# Motortreiber_3_4.net
KiCad netlist of a schematic drawn in Altium Designer
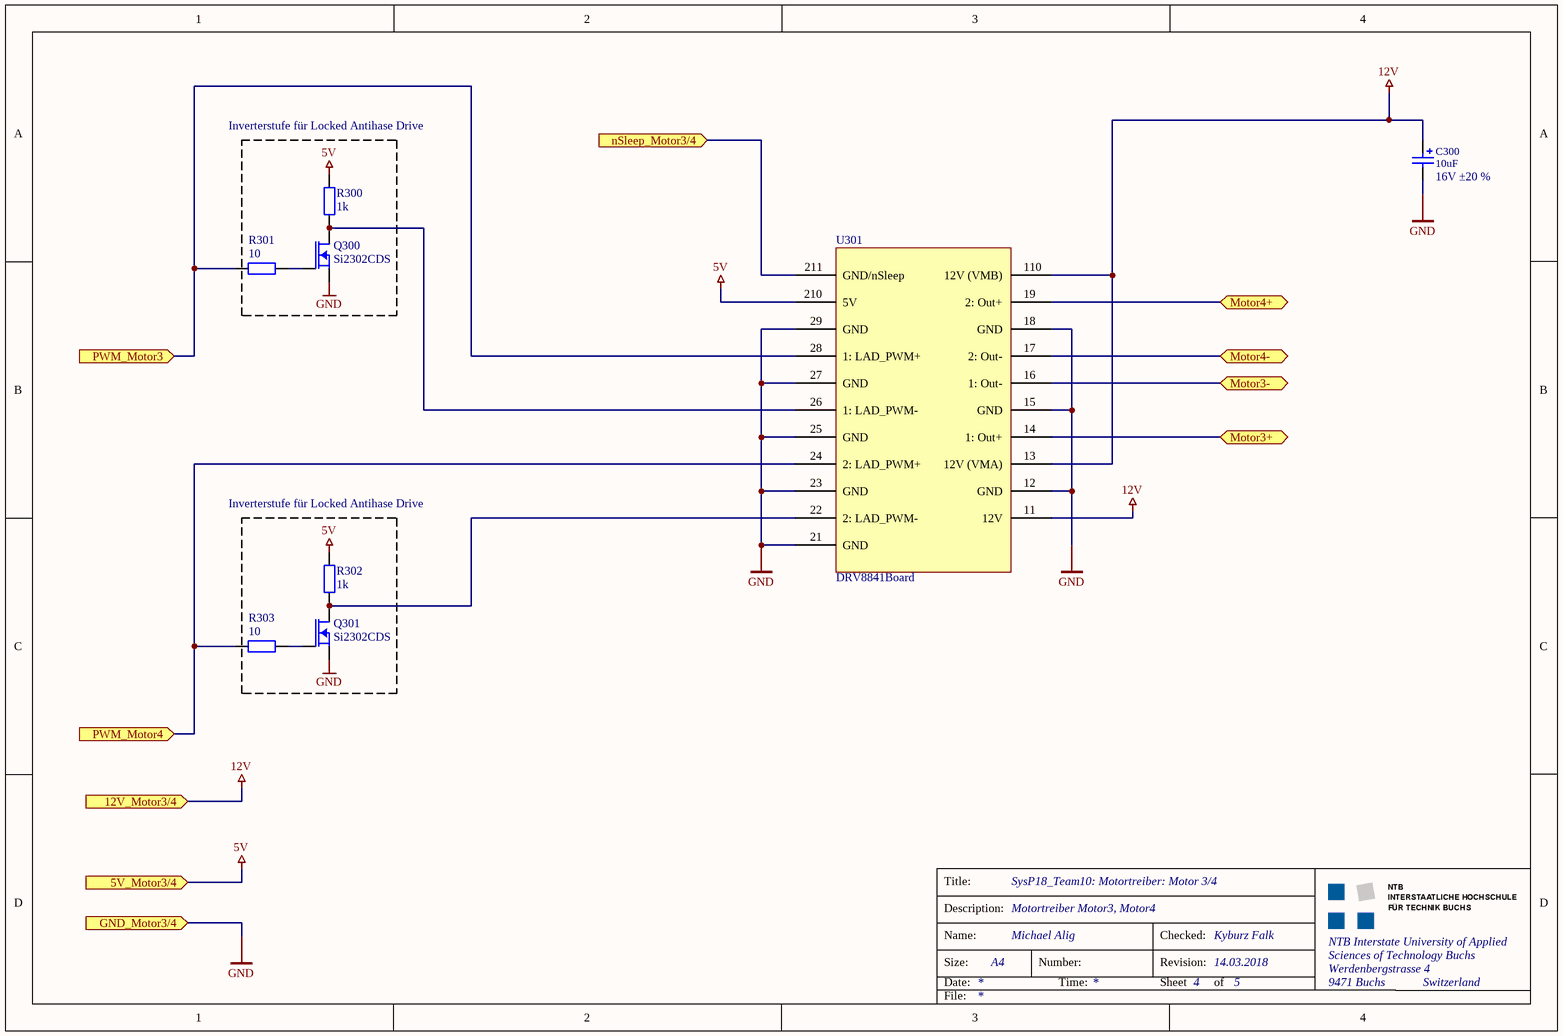
[diagram p0: Motortreiber_3,4.SchDoc]

(export (version "E")
  (design (tool "Eeschema 10.0.6"))
  (components
    (comp (ref "C300")
      (value "10uF")
      (footprint "CDE_CAP AVE CODE D_H")
      (description "Aluminum Electrolytic Capacitors for Filtering and Bypass, 47uF, 16V")
      (fields
        (field (name "MANUFACTURER") "Cornell Dubilier")
        (field (name "VALUEADDON") "16V ±20 %")
        (field (name "Comment") "AVE476M16D16T-F")
        (field (name "PUBLISHER") "Stefan Ursella, M.Eng")
      )
      (libsource (lib "Motorentreiber") (part "CDE_AVE476M16D16T-F_AVE CODE D"))
    )
    (comp (ref "Q300")
      (value "Si2302CDS")
      (footprint "SOT23-3")
      (description "N-Channel 20V (D-S) MOSFET")
      (libsource (lib "Motorentreiber") (part "Depletion Mode MOSFET"))
    )
    (comp (ref "Q301")
      (value "Si2302CDS")
      (footprint "SOT23-3")
      (description "N-Channel 20V (D-S) MOSFET")
      (libsource (lib "Motorentreiber") (part "Depletion Mode MOSFET"))
    )
    (comp (ref "R300")
      (value "1k")
      (footprint "GEN_R0805_H")
      (description "generic resistor")
      (fields
        (field (name "MANUFACTURER") "Tbd")
        (field (name "Comment") "Generic")
        (field (name "PUBLISHER") "Altium Limited")
      )
      (libsource (lib "") (part "GEN_R_2_1"))
    )
    (comp (ref "R301")
      (value "10")
      (footprint "GEN_R0805_H")
      (description "generic resistor")
      (fields
        (field (name "MANUFACTURER") "Tbd")
        (field (name "Comment") "Generic")
        (field (name "PUBLISHER") "Altium Limited")
      )
      (libsource (lib "Motorentreiber") (part "GEN_R_2"))
    )
    (comp (ref "R302")
      (value "1k")
      (footprint "GEN_R0805_H")
      (description "generic resistor")
      (fields
        (field (name "MANUFACTURER") "Tbd")
        (field (name "Comment") "Generic")
        (field (name "PUBLISHER") "Altium Limited")
      )
      (libsource (lib "") (part "GEN_R_2_1"))
    )
    (comp (ref "R303")
      (value "10")
      (footprint "GEN_R0805_H")
      (description "generic resistor")
      (fields
        (field (name "MANUFACTURER") "Tbd")
        (field (name "Comment") "Generic")
        (field (name "PUBLISHER") "Altium Limited")
      )
      (libsource (lib "Motorentreiber") (part "GEN_R_2"))
    )
    (comp (ref "U301")
      (value "DRV8841Board")
      (footprint "DRV8841_Board")
      (libsource (lib "Motorentreiber") (part "DRV8841_Board"))
    )
  )
  (nets
    (net (code "1") (name "/Motor3+") (class "Default")
      (node (ref "U301") (pin "14") (pinfunction "1:_Out+_14") (pintype "passive"))
    )
    (net (code "2") (name "/Motor3-") (class "Default")
      (node (ref "U301") (pin "16") (pinfunction "1:_Out-_16") (pintype "passive"))
    )
    (net (code "3") (name "/Motor4+") (class "Default")
      (node (ref "U301") (pin "19") (pinfunction "2:_Out+_19") (pintype "passive"))
    )
    (net (code "4") (name "/Motor4-") (class "Default")
      (node (ref "U301") (pin "17") (pinfunction "2:_Out-_17") (pintype "passive"))
    )
    (net (code "5") (name "/PWM_Motor3") (class "Default")
      (node (ref "R301") (pin "1") (pinfunction "1_1") (pintype "passive"))
      (node (ref "U301") (pin "28") (pinfunction "1:_LAD_PWM+_28") (pintype "passive"))
    )
    (net (code "6") (name "/PWM_Motor4") (class "Default")
      (node (ref "R303") (pin "1") (pinfunction "1_1") (pintype "passive"))
      (node (ref "U301") (pin "24") (pinfunction "2:_LAD_PWM+_24") (pintype "passive"))
    )
    (net (code "7") (name "/nSleep_Motor3{slash}4") (class "Default")
      (node (ref "U301") (pin "211") (pinfunction "GND/nSleep_211") (pintype "passive"))
    )
    (net (code "8") (name "5V") (class "Default")
      (node (ref "R300") (pin "2") (pinfunction "2_2") (pintype "passive"))
      (node (ref "R302") (pin "2") (pinfunction "2_2") (pintype "passive"))
      (node (ref "U301") (pin "210") (pinfunction "5V_210") (pintype "passive"))
    )
    (net (code "9") (name "12V") (class "Default")
      (node (ref "C300") (pin "1") (pinfunction "Pos_1") (pintype "passive"))
      (node (ref "U301") (pin "11") (pinfunction "12V_11") (pintype "passive"))
      (node (ref "U301") (pin "110") (pinfunction "12V_(VMB)_110") (pintype "passive"))
      (node (ref "U301") (pin "13") (pinfunction "12V_(VMA)_13") (pintype "passive"))
    )
    (net (code "10") (name "GND") (class "Default")
      (node (ref "C300") (pin "2") (pinfunction "Neg_2") (pintype "passive"))
      (node (ref "Q300") (pin "2") (pinfunction "S_2") (pintype "passive"))
      (node (ref "Q301") (pin "2") (pinfunction "S_2") (pintype "passive"))
      (node (ref "U301") (pin "12") (pinfunction "GND_12") (pintype "passive"))
      (node (ref "U301") (pin "15") (pinfunction "GND_15") (pintype "passive"))
      (node (ref "U301") (pin "18") (pinfunction "GND_18") (pintype "passive"))
      (node (ref "U301") (pin "21") (pinfunction "GND_21") (pintype "passive"))
      (node (ref "U301") (pin "23") (pinfunction "GND_23") (pintype "passive"))
      (node (ref "U301") (pin "25") (pinfunction "GND_25") (pintype "passive"))
      (node (ref "U301") (pin "27") (pinfunction "GND_27") (pintype "passive"))
      (node (ref "U301") (pin "29") (pinfunction "GND_29") (pintype "passive"))
    )
    (net (code "11") (name "Net-(Q300-D)") (class "Default")
      (node (ref "Q300") (pin "3") (pinfunction "D_3") (pintype "passive"))
      (node (ref "R300") (pin "1") (pinfunction "1_1") (pintype "passive"))
      (node (ref "U301") (pin "26") (pinfunction "1:_LAD_PWM-_26") (pintype "passive"))
    )
    (net (code "12") (name "Net-(Q300-G)") (class "Default")
      (node (ref "Q300") (pin "1") (pinfunction "G_1") (pintype "passive"))
      (node (ref "R301") (pin "2") (pinfunction "2_2") (pintype "passive"))
    )
    (net (code "13") (name "Net-(Q301-D)") (class "Default")
      (node (ref "Q301") (pin "3") (pinfunction "D_3") (pintype "passive"))
      (node (ref "R302") (pin "1") (pinfunction "1_1") (pintype "passive"))
      (node (ref "U301") (pin "22") (pinfunction "2:_LAD_PWM-_22") (pintype "passive"))
    )
    (net (code "14") (name "Net-(Q301-G)") (class "Default")
      (node (ref "Q301") (pin "1") (pinfunction "G_1") (pintype "passive"))
      (node (ref "R303") (pin "2") (pinfunction "2_2") (pintype "passive"))
    )
  )
)
